# core_app.net
KiCad netlist of a schematic drawn in Altium Designer
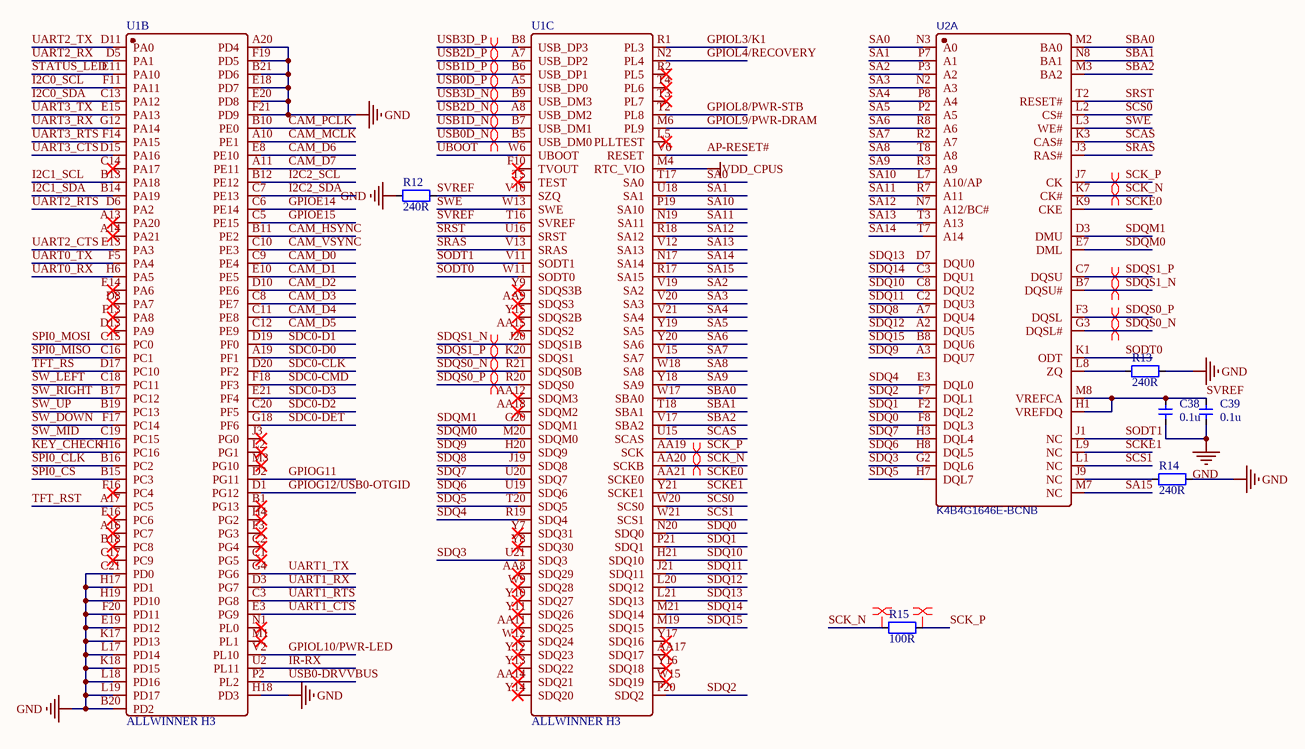
[diagram p0: core_app.SchDoc]

(export (version "E")
  (design (tool "Eeschema 10.0.6"))
  (components
    (comp (ref "C38")
      (value "0.1u")
      (footprint "C0402")
      (description "Capacitor")
      (fields (field (name "Comment") "CAP-0402"))
      (libsource (lib "core") (part "CAP-0402"))
    )
    (comp (ref "C39")
      (value "0.1u")
      (footprint "C0402")
      (description "Capacitor")
      (fields (field (name "Comment") "CAP-0402"))
      (libsource (lib "core") (part "CAP-0402"))
    )
    (comp (ref "R12")
      (value "240R")
      (footprint "R0402")
      (description "Resistor")
      (fields (field (name "Comment") "RES-0402"))
      (libsource (lib "core") (part "RES-0402"))
    )
    (comp (ref "R13")
      (value "240R")
      (footprint "R0402")
      (description "Resistor")
      (fields (field (name "Comment") "RES-0402"))
      (libsource (lib "core") (part "RES-0402"))
    )
    (comp (ref "R14")
      (value "240R")
      (footprint "R0402")
      (description "Resistor")
      (fields (field (name "Comment") "RES-0402"))
      (libsource (lib "core") (part "RES-0402"))
    )
    (comp (ref "R15")
      (value "100R")
      (footprint "R0402")
      (description "Resistor")
      (fields (field (name "Comment") "RES-0402"))
      (libsource (lib "core") (part "RES-0402"))
    )
    (comp (ref "U1")
      (value "ALLWINNER H3")
      (footprint "BGA-347_L14.0-W14.0-R21-C21-P0.65-TL")
      (libsource (lib "core") (part "allwinner H3"))
    )
    (comp (ref "U2")
      (value "K4B4G1646E-BCNB")
      (footprint "FBGA-96_L13.5-W7.5-R16-C6-P0.80-TL")
      (fields (field (name "BOM_SUPPLIER PART") "C2803248") (field (name "CONTRIBUTOR") "LCSC"))
      (libsource (lib "core") (part "K4B4G1646E-BCNB"))
    )
  )
  (nets
    (net (code "1") (name "/AP-RESET#") (class "Default")
      (node (ref "U1") (pin "V6") (pinfunction "RESET_V6") (pintype "passive"))
    )
    (net (code "2") (name "/CAM_D0") (class "Default")
      (node (ref "U1") (pin "C9") (pinfunction "PE4_C9") (pintype "passive"))
    )
    (net (code "3") (name "/CAM_D1") (class "Default")
      (node (ref "U1") (pin "E10") (pinfunction "PE5_E10") (pintype "passive"))
    )
    (net (code "4") (name "/CAM_D2") (class "Default")
      (node (ref "U1") (pin "D10") (pinfunction "PE6_D10") (pintype "passive"))
    )
    (net (code "5") (name "/CAM_D3") (class "Default")
      (node (ref "U1") (pin "C8") (pinfunction "PE7_C8") (pintype "passive"))
    )
    (net (code "6") (name "/CAM_D4") (class "Default")
      (node (ref "U1") (pin "C11") (pinfunction "PE8_C11") (pintype "passive"))
    )
    (net (code "7") (name "/CAM_D5") (class "Default")
      (node (ref "U1") (pin "C12") (pinfunction "PE9_C12") (pintype "passive"))
    )
    (net (code "8") (name "/CAM_D6") (class "Default")
      (node (ref "U1") (pin "E8") (pinfunction "PE10_E8") (pintype "passive"))
    )
    (net (code "9") (name "/CAM_D7") (class "Default")
      (node (ref "U1") (pin "A11") (pinfunction "PE11_A11") (pintype "passive"))
    )
    (net (code "10") (name "/CAM_HSYNC") (class "Default")
      (node (ref "U1") (pin "B11") (pinfunction "PE2_B11") (pintype "passive"))
    )
    (net (code "11") (name "/CAM_MCLK") (class "Default")
      (node (ref "U1") (pin "A10") (pinfunction "PE1_A10") (pintype "passive"))
    )
    (net (code "12") (name "/CAM_PCLK") (class "Default")
      (node (ref "U1") (pin "B10") (pinfunction "PE0_B10") (pintype "passive"))
    )
    (net (code "13") (name "/CAM_VSYNC") (class "Default")
      (node (ref "U1") (pin "C10") (pinfunction "PE3_C10") (pintype "passive"))
    )
    (net (code "14") (name "/GPIOE14") (class "Default")
      (node (ref "U1") (pin "C6") (pinfunction "PE14_C6") (pintype "passive"))
    )
    (net (code "15") (name "/GPIOE15") (class "Default")
      (node (ref "U1") (pin "C5") (pinfunction "PE15_C5") (pintype "passive"))
    )
    (net (code "16") (name "/GPIOG11") (class "Default")
      (node (ref "U1") (pin "D2") (pinfunction "PG11_D2") (pintype "passive"))
    )
    (net (code "17") (name "/GPIOG12{slash}USB0-OTGID") (class "Default")
      (node (ref "U1") (pin "D1") (pinfunction "PG12_D1") (pintype "passive"))
    )
    (net (code "18") (name "/GPIOL3{slash}K1") (class "Default")
      (node (ref "U1") (pin "R1") (pinfunction "PL3_R1") (pintype "passive"))
    )
    (net (code "19") (name "/GPIOL4{slash}RECOVERY") (class "Default")
      (node (ref "U1") (pin "N2") (pinfunction "PL4_N2") (pintype "passive"))
    )
    (net (code "20") (name "/GPIOL8{slash}PWR-STB") (class "Default")
      (node (ref "U1") (pin "T2") (pinfunction "PL8_T2") (pintype "passive"))
    )
    (net (code "21") (name "/GPIOL9{slash}PWR-DRAM") (class "Default")
      (node (ref "U1") (pin "M6") (pinfunction "PL9_M6") (pintype "passive"))
    )
    (net (code "22") (name "/GPIOL10{slash}PWR-LED") (class "Default")
      (node (ref "U1") (pin "V2") (pinfunction "PL10_V2") (pintype "passive"))
    )
    (net (code "23") (name "/I2C0_SCL") (class "Default")
      (node (ref "U1") (pin "F11") (pinfunction "PA11_F11") (pintype "passive"))
    )
    (net (code "24") (name "/I2C0_SDA") (class "Default")
      (node (ref "U1") (pin "C13") (pinfunction "PA12_C13") (pintype "passive"))
    )
    (net (code "25") (name "/I2C1_SCL") (class "Default")
      (node (ref "U1") (pin "B13") (pinfunction "PA18_B13") (pintype "passive"))
    )
    (net (code "26") (name "/I2C1_SDA") (class "Default")
      (node (ref "U1") (pin "B14") (pinfunction "PA19_B14") (pintype "passive"))
    )
    (net (code "27") (name "/I2C2_SCL") (class "Default")
      (node (ref "U1") (pin "B12") (pinfunction "PE12_B12") (pintype "passive"))
    )
    (net (code "28") (name "/I2C2_SDA") (class "Default")
      (node (ref "U1") (pin "C7") (pinfunction "PE13_C7") (pintype "passive"))
    )
    (net (code "29") (name "/IR-RX") (class "Default")
      (node (ref "U1") (pin "U2") (pinfunction "PL11_U2") (pintype "passive"))
    )
    (net (code "30") (name "/KEY_CHECK") (class "Default")
      (node (ref "U1") (pin "H16") (pinfunction "PC16_H16") (pintype "passive"))
    )
    (net (code "31") (name "/SA0") (class "Default")
      (node (ref "U1") (pin "T17") (pinfunction "SA0_T17") (pintype "passive"))
      (node (ref "U2") (pin "N3") (pinfunction "A0_N3") (pintype "passive"))
    )
    (net (code "32") (name "/SA1") (class "Default")
      (node (ref "U1") (pin "U18") (pinfunction "SA1_U18") (pintype "passive"))
      (node (ref "U2") (pin "P7") (pinfunction "A1_P7") (pintype "passive"))
    )
    (net (code "33") (name "/SA2") (class "Default")
      (node (ref "U1") (pin "V19") (pinfunction "SA2_V19") (pintype "passive"))
      (node (ref "U2") (pin "P3") (pinfunction "A2_P3") (pintype "passive"))
    )
    (net (code "34") (name "/SA3") (class "Default")
      (node (ref "U1") (pin "V20") (pinfunction "SA3_V20") (pintype "passive"))
      (node (ref "U2") (pin "N2") (pinfunction "A3_N2") (pintype "passive"))
    )
    (net (code "35") (name "/SA4") (class "Default")
      (node (ref "U1") (pin "V21") (pinfunction "SA4_V21") (pintype "passive"))
      (node (ref "U2") (pin "P8") (pinfunction "A4_P8") (pintype "passive"))
    )
    (net (code "36") (name "/SA5") (class "Default")
      (node (ref "U1") (pin "Y19") (pinfunction "SA5_Y19") (pintype "passive"))
      (node (ref "U2") (pin "P2") (pinfunction "A5_P2") (pintype "passive"))
    )
    (net (code "37") (name "/SA6") (class "Default")
      (node (ref "U1") (pin "Y20") (pinfunction "SA6_Y20") (pintype "passive"))
      (node (ref "U2") (pin "R8") (pinfunction "A6_R8") (pintype "passive"))
    )
    (net (code "38") (name "/SA7") (class "Default")
      (node (ref "U1") (pin "V15") (pinfunction "SA7_V15") (pintype "passive"))
      (node (ref "U2") (pin "R2") (pinfunction "A7_R2") (pintype "passive"))
    )
    (net (code "39") (name "/SA8") (class "Default")
      (node (ref "U1") (pin "W18") (pinfunction "SA8_W18") (pintype "passive"))
      (node (ref "U2") (pin "T8") (pinfunction "A8_T8") (pintype "passive"))
    )
    (net (code "40") (name "/SA9") (class "Default")
      (node (ref "U1") (pin "Y18") (pinfunction "SA9_Y18") (pintype "passive"))
      (node (ref "U2") (pin "R3") (pinfunction "A9_R3") (pintype "passive"))
    )
    (net (code "41") (name "/SA10") (class "Default")
      (node (ref "U1") (pin "P19") (pinfunction "SA10_P19") (pintype "passive"))
      (node (ref "U2") (pin "L7") (pinfunction "A10/AP_L7") (pintype "passive"))
    )
    (net (code "42") (name "/SA11") (class "Default")
      (node (ref "U1") (pin "N19") (pinfunction "SA11_N19") (pintype "passive"))
      (node (ref "U2") (pin "R7") (pinfunction "A11_R7") (pintype "passive"))
    )
    (net (code "43") (name "/SA12") (class "Default")
      (node (ref "U1") (pin "R18") (pinfunction "SA12_R18") (pintype "passive"))
      (node (ref "U2") (pin "N7") (pinfunction "A12/BC#_N7") (pintype "passive"))
    )
    (net (code "44") (name "/SA13") (class "Default")
      (node (ref "U1") (pin "V12") (pinfunction "SA13_V12") (pintype "passive"))
      (node (ref "U2") (pin "T3") (pinfunction "A13_T3") (pintype "passive"))
    )
    (net (code "45") (name "/SA14") (class "Default")
      (node (ref "U1") (pin "N17") (pinfunction "SA14_N17") (pintype "passive"))
      (node (ref "U2") (pin "T7") (pinfunction "A14_T7") (pintype "passive"))
    )
    (net (code "46") (name "/SA15") (class "Default")
      (node (ref "U1") (pin "R17") (pinfunction "SA15_R17") (pintype "passive"))
      (node (ref "U2") (pin "M7") (pinfunction "NC_M7") (pintype "passive"))
    )
    (net (code "47") (name "/SBA0") (class "Default")
      (node (ref "U1") (pin "W17") (pinfunction "SBA0_W17") (pintype "passive"))
      (node (ref "U2") (pin "M2") (pinfunction "BA0_M2") (pintype "passive"))
    )
    (net (code "48") (name "/SBA1") (class "Default")
      (node (ref "U1") (pin "T18") (pinfunction "SBA1_T18") (pintype "passive"))
      (node (ref "U2") (pin "N8") (pinfunction "BA1_N8") (pintype "passive"))
    )
    (net (code "49") (name "/SBA2") (class "Default")
      (node (ref "U1") (pin "V17") (pinfunction "SBA2_V17") (pintype "passive"))
      (node (ref "U2") (pin "M3") (pinfunction "BA2_M3") (pintype "passive"))
    )
    (net (code "50") (name "/SCAS") (class "Default")
      (node (ref "U1") (pin "U15") (pinfunction "SCAS_U15") (pintype "passive"))
      (node (ref "U2") (pin "K3") (pinfunction "CAS#_K3") (pintype "passive"))
    )
    (net (code "51") (name "/SCKE0") (class "Default")
      (node (ref "U1") (pin "AA21") (pinfunction "SCKE0_AA21") (pintype "passive"))
      (node (ref "U2") (pin "K9") (pinfunction "CKE_K9") (pintype "passive"))
    )
    (net (code "52") (name "/SCKE1") (class "Default")
      (node (ref "U1") (pin "Y21") (pinfunction "SCKE1_Y21") (pintype "passive"))
      (node (ref "U2") (pin "L9") (pinfunction "NC_L9") (pintype "passive"))
    )
    (net (code "53") (name "/SCK_N") (class "Default")
      (node (ref "R15") (pin "2") (pinfunction "2_2") (pintype "passive"))
      (node (ref "U1") (pin "AA20") (pinfunction "SCKB_AA20") (pintype "passive"))
      (node (ref "U2") (pin "K7") (pinfunction "CK#_K7") (pintype "passive"))
    )
    (net (code "54") (name "/SCK_P") (class "Default")
      (node (ref "R15") (pin "1") (pinfunction "1_1") (pintype "passive"))
      (node (ref "U1") (pin "AA19") (pinfunction "SCK_AA19") (pintype "passive"))
      (node (ref "U2") (pin "J7") (pinfunction "CK_J7") (pintype "passive"))
    )
    (net (code "55") (name "/SCS0") (class "Default")
      (node (ref "U1") (pin "W20") (pinfunction "SCS0_W20") (pintype "passive"))
      (node (ref "U2") (pin "L2") (pinfunction "CS#_L2") (pintype "passive"))
    )
    (net (code "56") (name "/SCS1") (class "Default")
      (node (ref "U1") (pin "W21") (pinfunction "SCS1_W21") (pintype "passive"))
      (node (ref "U2") (pin "L1") (pinfunction "NC_L1") (pintype "passive"))
    )
    (net (code "57") (name "/SDC0-CLK") (class "Default")
      (node (ref "U1") (pin "D20") (pinfunction "PF2_D20") (pintype "passive"))
    )
    (net (code "58") (name "/SDC0-CMD") (class "Default")
      (node (ref "U1") (pin "F18") (pinfunction "PF3_F18") (pintype "passive"))
    )
    (net (code "59") (name "/SDC0-D0") (class "Default")
      (node (ref "U1") (pin "A19") (pinfunction "PF1_A19") (pintype "passive"))
    )
    (net (code "60") (name "/SDC0-D1") (class "Default")
      (node (ref "U1") (pin "D19") (pinfunction "PF0_D19") (pintype "passive"))
    )
    (net (code "61") (name "/SDC0-D2") (class "Default")
      (node (ref "U1") (pin "C20") (pinfunction "PF5_C20") (pintype "passive"))
    )
    (net (code "62") (name "/SDC0-D3") (class "Default")
      (node (ref "U1") (pin "E21") (pinfunction "PF4_E21") (pintype "passive"))
    )
    (net (code "63") (name "/SDC0-DET") (class "Default")
      (node (ref "U1") (pin "G18") (pinfunction "PF6_G18") (pintype "passive"))
    )
    (net (code "64") (name "/SDQ0") (class "Default")
      (node (ref "U1") (pin "N20") (pinfunction "SDQ0_N20") (pintype "passive"))
      (node (ref "U2") (pin "F8") (pinfunction "DQL3_F8") (pintype "passive"))
    )
    (net (code "65") (name "/SDQ1") (class "Default")
      (node (ref "U1") (pin "P21") (pinfunction "SDQ1_P21") (pintype "passive"))
      (node (ref "U2") (pin "F2") (pinfunction "DQL2_F2") (pintype "passive"))
    )
    (net (code "66") (name "/SDQ2") (class "Default")
      (node (ref "U1") (pin "P20") (pinfunction "SDQ2_P20") (pintype "passive"))
      (node (ref "U2") (pin "F7") (pinfunction "DQL1_F7") (pintype "passive"))
    )
    (net (code "67") (name "/SDQ3") (class "Default")
      (node (ref "U1") (pin "U21") (pinfunction "SDQ3_U21") (pintype "passive"))
      (node (ref "U2") (pin "G2") (pinfunction "DQL6_G2") (pintype "passive"))
    )
    (net (code "68") (name "/SDQ4") (class "Default")
      (node (ref "U1") (pin "R19") (pinfunction "SDQ4_R19") (pintype "passive"))
      (node (ref "U2") (pin "E3") (pinfunction "DQL0_E3") (pintype "passive"))
    )
    (net (code "69") (name "/SDQ5") (class "Default")
      (node (ref "U1") (pin "T20") (pinfunction "SDQ5_T20") (pintype "passive"))
      (node (ref "U2") (pin "H7") (pinfunction "DQL7_H7") (pintype "passive"))
    )
    (net (code "70") (name "/SDQ6") (class "Default")
      (node (ref "U1") (pin "U19") (pinfunction "SDQ6_U19") (pintype "passive"))
      (node (ref "U2") (pin "H8") (pinfunction "DQL5_H8") (pintype "passive"))
    )
    (net (code "71") (name "/SDQ7") (class "Default")
      (node (ref "U1") (pin "U20") (pinfunction "SDQ7_U20") (pintype "passive"))
      (node (ref "U2") (pin "H3") (pinfunction "DQL4_H3") (pintype "passive"))
    )
    (net (code "72") (name "/SDQ8") (class "Default")
      (node (ref "U1") (pin "J19") (pinfunction "SDQ8_J19") (pintype "passive"))
      (node (ref "U2") (pin "A7") (pinfunction "DQU4_A7") (pintype "passive"))
    )
    (net (code "73") (name "/SDQ9") (class "Default")
      (node (ref "U1") (pin "H20") (pinfunction "SDQ9_H20") (pintype "passive"))
      (node (ref "U2") (pin "A3") (pinfunction "DQU7_A3") (pintype "passive"))
    )
    (net (code "74") (name "/SDQ10") (class "Default")
      (node (ref "U1") (pin "H21") (pinfunction "SDQ10_H21") (pintype "passive"))
      (node (ref "U2") (pin "C8") (pinfunction "DQU2_C8") (pintype "passive"))
    )
    (net (code "75") (name "/SDQ11") (class "Default")
      (node (ref "U1") (pin "J21") (pinfunction "SDQ11_J21") (pintype "passive"))
      (node (ref "U2") (pin "C2") (pinfunction "DQU3_C2") (pintype "passive"))
    )
    (net (code "76") (name "/SDQ12") (class "Default")
      (node (ref "U1") (pin "L20") (pinfunction "SDQ12_L20") (pintype "passive"))
      (node (ref "U2") (pin "A2") (pinfunction "DQU5_A2") (pintype "passive"))
    )
    (net (code "77") (name "/SDQ13") (class "Default")
      (node (ref "U1") (pin "L21") (pinfunction "SDQ13_L21") (pintype "passive"))
      (node (ref "U2") (pin "D7") (pinfunction "DQU0_D7") (pintype "passive"))
    )
    (net (code "78") (name "/SDQ14") (class "Default")
      (node (ref "U1") (pin "M21") (pinfunction "SDQ14_M21") (pintype "passive"))
      (node (ref "U2") (pin "C3") (pinfunction "DQU1_C3") (pintype "passive"))
    )
    (net (code "79") (name "/SDQ15") (class "Default")
      (node (ref "U1") (pin "M19") (pinfunction "SDQ15_M19") (pintype "passive"))
      (node (ref "U2") (pin "B8") (pinfunction "DQU6_B8") (pintype "passive"))
    )
    (net (code "80") (name "/SDQM0") (class "Default")
      (node (ref "U1") (pin "M20") (pinfunction "SDQM0_M20") (pintype "passive"))
      (node (ref "U2") (pin "E7") (pinfunction "DML_E7") (pintype "passive"))
    )
    (net (code "81") (name "/SDQM1") (class "Default")
      (node (ref "U1") (pin "G20") (pinfunction "SDQM1_G20") (pintype "passive"))
      (node (ref "U2") (pin "D3") (pinfunction "DMU_D3") (pintype "passive"))
    )
    (net (code "82") (name "/SDQS0_N") (class "Default")
      (node (ref "U1") (pin "R21") (pinfunction "SDQS0B_R21") (pintype "passive"))
      (node (ref "U2") (pin "G3") (pinfunction "DQSL#_G3") (pintype "passive"))
    )
    (net (code "83") (name "/SDQS0_P") (class "Default")
      (node (ref "U1") (pin "R20") (pinfunction "SDQS0_R20") (pintype "passive"))
      (node (ref "U2") (pin "F3") (pinfunction "DQSL_F3") (pintype "passive"))
    )
    (net (code "84") (name "/SDQS1_N") (class "Default")
      (node (ref "U1") (pin "J20") (pinfunction "SDQS1B_J20") (pintype "passive"))
      (node (ref "U2") (pin "B7") (pinfunction "DQSU#_B7") (pintype "passive"))
    )
    (net (code "85") (name "/SDQS1_P") (class "Default")
      (node (ref "U1") (pin "K20") (pinfunction "SDQS1_K20") (pintype "passive"))
      (node (ref "U2") (pin "C7") (pinfunction "DQSU_C7") (pintype "passive"))
    )
    (net (code "86") (name "/SODT0") (class "Default")
      (node (ref "U1") (pin "W11") (pinfunction "SODT0_W11") (pintype "passive"))
      (node (ref "U2") (pin "K1") (pinfunction "ODT_K1") (pintype "passive"))
    )
    (net (code "87") (name "/SODT1") (class "Default")
      (node (ref "U1") (pin "V11") (pinfunction "SODT1_V11") (pintype "passive"))
      (node (ref "U2") (pin "J1") (pinfunction "NC_J1") (pintype "passive"))
    )
    (net (code "88") (name "/SPI0_CLK") (class "Default")
      (node (ref "U1") (pin "B16") (pinfunction "PC2_B16") (pintype "passive"))
    )
    (net (code "89") (name "/SPI0_CS") (class "Default")
      (node (ref "U1") (pin "B15") (pinfunction "PC3_B15") (pintype "passive"))
    )
    (net (code "90") (name "/SPI0_MISO") (class "Default")
      (node (ref "U1") (pin "C16") (pinfunction "PC1_C16") (pintype "passive"))
    )
    (net (code "91") (name "/SPI0_MOSI") (class "Default")
      (node (ref "U1") (pin "C15") (pinfunction "PC0_C15") (pintype "passive"))
    )
    (net (code "92") (name "/SRAS") (class "Default")
      (node (ref "U1") (pin "V13") (pinfunction "SRAS_V13") (pintype "passive"))
      (node (ref "U2") (pin "J3") (pinfunction "RAS#_J3") (pintype "passive"))
    )
    (net (code "93") (name "/SRST") (class "Default")
      (node (ref "U1") (pin "U16") (pinfunction "SRST_U16") (pintype "passive"))
      (node (ref "U2") (pin "T2") (pinfunction "RESET#_T2") (pintype "passive"))
    )
    (net (code "94") (name "/STATUS_LED") (class "Default")
      (node (ref "U1") (pin "E11") (pinfunction "PA10_E11") (pintype "passive"))
    )
    (net (code "95") (name "/SVREF") (class "Default")
      (node (ref "C38") (pin "2") (pinfunction "2_2") (pintype "passive"))
      (node (ref "C39") (pin "2") (pinfunction "2_2") (pintype "passive"))
      (node (ref "R12") (pin "1") (pinfunction "1_1") (pintype "passive"))
      (node (ref "U1") (pin "T16") (pinfunction "SVREF_T16") (pintype "passive"))
      (node (ref "U1") (pin "V10") (pinfunction "SZQ_V10") (pintype "passive"))
      (node (ref "U2") (pin "H1") (pinfunction "VREFDQ_H1") (pintype "passive"))
      (node (ref "U2") (pin "M8") (pinfunction "VREFCA_M8") (pintype "passive"))
    )
    (net (code "96") (name "/SWE") (class "Default")
      (node (ref "U1") (pin "W13") (pinfunction "SWE_W13") (pintype "passive"))
      (node (ref "U2") (pin "L3") (pinfunction "WE#_L3") (pintype "passive"))
    )
    (net (code "97") (name "/SW_DOWN") (class "Default")
      (node (ref "U1") (pin "F17") (pinfunction "PC14_F17") (pintype "passive"))
    )
    (net (code "98") (name "/SW_LEFT") (class "Default")
      (node (ref "U1") (pin "C18") (pinfunction "PC11_C18") (pintype "passive"))
    )
    (net (code "99") (name "/SW_MID") (class "Default")
      (node (ref "U1") (pin "C19") (pinfunction "PC15_C19") (pintype "passive"))
    )
    (net (code "100") (name "/SW_RIGHT") (class "Default")
      (node (ref "U1") (pin "B17") (pinfunction "PC12_B17") (pintype "passive"))
    )
    (net (code "101") (name "/SW_UP") (class "Default")
      (node (ref "U1") (pin "B19") (pinfunction "PC13_B19") (pintype "passive"))
    )
    (net (code "102") (name "/TFT_RS") (class "Default")
      (node (ref "U1") (pin "D17") (pinfunction "PC10_D17") (pintype "passive"))
    )
    (net (code "103") (name "/TFT_RST") (class "Default")
      (node (ref "U1") (pin "A17") (pinfunction "PC5_A17") (pintype "passive"))
    )
    (net (code "104") (name "/UART0_RX") (class "Default")
      (node (ref "U1") (pin "H6") (pinfunction "PA5_H6") (pintype "passive"))
    )
    (net (code "105") (name "/UART0_TX") (class "Default")
      (node (ref "U1") (pin "F5") (pinfunction "PA4_F5") (pintype "passive"))
    )
    (net (code "106") (name "/UART1_CTS") (class "Default")
      (node (ref "U1") (pin "E3") (pinfunction "PG9_E3") (pintype "passive"))
    )
    (net (code "107") (name "/UART1_RTS") (class "Default")
      (node (ref "U1") (pin "C3") (pinfunction "PG8_C3") (pintype "passive"))
    )
    (net (code "108") (name "/UART1_RX") (class "Default")
      (node (ref "U1") (pin "D3") (pinfunction "PG7_D3") (pintype "passive"))
    )
    (net (code "109") (name "/UART1_TX") (class "Default")
      (node (ref "U1") (pin "G4") (pinfunction "PG6_G4") (pintype "passive"))
    )
    (net (code "110") (name "/UART2_CTS") (class "Default")
      (node (ref "U1") (pin "E13") (pinfunction "PA3_E13") (pintype "passive"))
    )
    (net (code "111") (name "/UART2_RTS") (class "Default")
      (node (ref "U1") (pin "D6") (pinfunction "PA2_D6") (pintype "passive"))
    )
    (net (code "112") (name "/UART2_RX") (class "Default")
      (node (ref "U1") (pin "D5") (pinfunction "PA1_D5") (pintype "passive"))
    )
    (net (code "113") (name "/UART2_TX") (class "Default")
      (node (ref "U1") (pin "D11") (pinfunction "PA0_D11") (pintype "passive"))
    )
    (net (code "114") (name "/UART3_CTS") (class "Default")
      (node (ref "U1") (pin "D15") (pinfunction "PA16_D15") (pintype "passive"))
    )
    (net (code "115") (name "/UART3_RTS") (class "Default")
      (node (ref "U1") (pin "F14") (pinfunction "PA15_F14") (pintype "passive"))
    )
    (net (code "116") (name "/UART3_RX") (class "Default")
      (node (ref "U1") (pin "G12") (pinfunction "PA14_G12") (pintype "passive"))
    )
    (net (code "117") (name "/UART3_TX") (class "Default")
      (node (ref "U1") (pin "E15") (pinfunction "PA13_E15") (pintype "passive"))
    )
    (net (code "118") (name "/UBOOT") (class "Default")
      (node (ref "U1") (pin "W6") (pinfunction "UBOOT_W6") (pintype "passive"))
    )
    (net (code "119") (name "/USB0-DRVVBUS") (class "Default")
      (node (ref "U1") (pin "P2") (pinfunction "PL2_P2") (pintype "passive"))
    )
    (net (code "120") (name "/USB0D_N") (class "Default")
      (node (ref "U1") (pin "B5") (pinfunction "USB_DM0_B5") (pintype "passive"))
    )
    (net (code "121") (name "/USB0D_P") (class "Default")
      (node (ref "U1") (pin "A5") (pinfunction "USB_DP0_A5") (pintype "passive"))
    )
    (net (code "122") (name "/USB1D_N") (class "Default")
      (node (ref "U1") (pin "B7") (pinfunction "USB_DM1_B7") (pintype "passive"))
    )
    (net (code "123") (name "/USB1D_P") (class "Default")
      (node (ref "U1") (pin "B6") (pinfunction "USB_DP1_B6") (pintype "passive"))
    )
    (net (code "124") (name "/USB2D_N") (class "Default")
      (node (ref "U1") (pin "A8") (pinfunction "USB_DM2_A8") (pintype "passive"))
    )
    (net (code "125") (name "/USB2D_P") (class "Default")
      (node (ref "U1") (pin "A7") (pinfunction "USB_DP2_A7") (pintype "passive"))
    )
    (net (code "126") (name "/USB3D_N") (class "Default")
      (node (ref "U1") (pin "B9") (pinfunction "USB_DM3_B9") (pintype "passive"))
    )
    (net (code "127") (name "/USB3D_P") (class "Default")
      (node (ref "U1") (pin "B8") (pinfunction "USB_DP3_B8") (pintype "passive"))
    )
    (net (code "128") (name "GND") (class "Default")
      (node (ref "C38") (pin "1") (pinfunction "1_1") (pintype "passive"))
      (node (ref "C39") (pin "1") (pinfunction "1_1") (pintype "passive"))
      (node (ref "R12") (pin "2") (pinfunction "2_2") (pintype "passive"))
      (node (ref "R13") (pin "1") (pinfunction "1_1") (pintype "passive"))
      (node (ref "R14") (pin "1") (pinfunction "1_1") (pintype "passive"))
      (node (ref "U1") (pin "A20") (pinfunction "PD4_A20") (pintype "passive"))
      (node (ref "U1") (pin "B20") (pinfunction "PD2_B20") (pintype "passive"))
      (node (ref "U1") (pin "B21") (pinfunction "PD6_B21") (pintype "passive"))
      (node (ref "U1") (pin "C21") (pinfunction "PD0_C21") (pintype "passive"))
      (node (ref "U1") (pin "E18") (pinfunction "PD7_E18") (pintype "passive"))
      (node (ref "U1") (pin "E19") (pinfunction "PD12_E19") (pintype "passive"))
      (node (ref "U1") (pin "E20") (pinfunction "PD8_E20") (pintype "passive"))
      (node (ref "U1") (pin "F19") (pinfunction "PD5_F19") (pintype "passive"))
      (node (ref "U1") (pin "F20") (pinfunction "PD11_F20") (pintype "passive"))
      (node (ref "U1") (pin "F21") (pinfunction "PD9_F21") (pintype "passive"))
      (node (ref "U1") (pin "H17") (pinfunction "PD1_H17") (pintype "passive"))
      (node (ref "U1") (pin "H18") (pinfunction "PD3_H18") (pintype "passive"))
      (node (ref "U1") (pin "H19") (pinfunction "PD10_H19") (pintype "passive"))
      (node (ref "U1") (pin "K17") (pinfunction "PD13_K17") (pintype "passive"))
      (node (ref "U1") (pin "K18") (pinfunction "PD15_K18") (pintype "passive"))
      (node (ref "U1") (pin "L17") (pinfunction "PD14_L17") (pintype "passive"))
      (node (ref "U1") (pin "L18") (pinfunction "PD16_L18") (pintype "passive"))
      (node (ref "U1") (pin "L19") (pinfunction "PD17_L19") (pintype "passive"))
    )
    (net (code "129") (name "Net-(R14-Pad2)") (class "Default")
      (node (ref "R14") (pin "2") (pinfunction "2_2") (pintype "passive"))
      (node (ref "U2") (pin "J9") (pinfunction "NC_J9") (pintype "passive"))
    )
    (net (code "130") (name "Net-(U2A-ZQ)") (class "Default")
      (node (ref "R13") (pin "2") (pinfunction "2_2") (pintype "passive"))
      (node (ref "U2") (pin "L8") (pinfunction "ZQ_L8") (pintype "passive"))
    )
    (net (code "131") (name "VDD_CPUS") (class "Default")
      (node (ref "U1") (pin "M4") (pinfunction "RTC_VIO_M4") (pintype "passive"))
    )
    (net (code "132") (name "unconnected-(U1B-PA6-PadE14)") (class "Default")
      (node (ref "U1") (pin "E14") (pinfunction "PA6_E14") (pintype "passive+no_connect"))
    )
    (net (code "133") (name "unconnected-(U1B-PA7-PadD8)") (class "Default")
      (node (ref "U1") (pin "D8") (pinfunction "PA7_D8") (pintype "passive+no_connect"))
    )
    (net (code "134") (name "unconnected-(U1B-PA8-PadF13)") (class "Default")
      (node (ref "U1") (pin "F13") (pinfunction "PA8_F13") (pintype "passive+no_connect"))
    )
    (net (code "135") (name "unconnected-(U1B-PA9-PadD13)") (class "Default")
      (node (ref "U1") (pin "D13") (pinfunction "PA9_D13") (pintype "passive+no_connect"))
    )
    (net (code "136") (name "unconnected-(U1B-PA17-PadC14)") (class "Default")
      (node (ref "U1") (pin "C14") (pinfunction "PA17_C14") (pintype "passive+no_connect"))
    )
    (net (code "137") (name "unconnected-(U1B-PA20-PadA13)") (class "Default")
      (node (ref "U1") (pin "A13") (pinfunction "PA20_A13") (pintype "passive+no_connect"))
    )
    (net (code "138") (name "unconnected-(U1B-PA21-PadA14)") (class "Default")
      (node (ref "U1") (pin "A14") (pinfunction "PA21_A14") (pintype "passive+no_connect"))
    )
    (net (code "139") (name "unconnected-(U1B-PC4-PadF16)") (class "Default")
      (node (ref "U1") (pin "F16") (pinfunction "PC4_F16") (pintype "passive+no_connect"))
    )
    (net (code "140") (name "unconnected-(U1B-PC6-PadE16)") (class "Default")
      (node (ref "U1") (pin "E16") (pinfunction "PC6_E16") (pintype "passive+no_connect"))
    )
    (net (code "141") (name "unconnected-(U1B-PC7-PadA16)") (class "Default")
      (node (ref "U1") (pin "A16") (pinfunction "PC7_A16") (pintype "passive+no_connect"))
    )
    (net (code "142") (name "unconnected-(U1B-PC8-PadB18)") (class "Default")
      (node (ref "U1") (pin "B18") (pinfunction "PC8_B18") (pintype "passive+no_connect"))
    )
    (net (code "143") (name "unconnected-(U1B-PC9-PadC17)") (class "Default")
      (node (ref "U1") (pin "C17") (pinfunction "PC9_C17") (pintype "passive+no_connect"))
    )
    (net (code "144") (name "unconnected-(U1B-PG0-PadJ3)") (class "Default")
      (node (ref "U1") (pin "J3") (pinfunction "PG0_J3") (pintype "passive+no_connect"))
    )
    (net (code "145") (name "unconnected-(U1B-PG1-PadL2)") (class "Default")
      (node (ref "U1") (pin "L2") (pinfunction "PG1_L2") (pintype "passive+no_connect"))
    )
    (net (code "146") (name "unconnected-(U1B-PG2-PadH4)") (class "Default")
      (node (ref "U1") (pin "H4") (pinfunction "PG2_H4") (pintype "passive+no_connect"))
    )
    (net (code "147") (name "unconnected-(U1B-PG3-PadF3)") (class "Default")
      (node (ref "U1") (pin "F3") (pinfunction "PG3_F3") (pintype "passive+no_connect"))
    )
    (net (code "148") (name "unconnected-(U1B-PG4-PadC2)") (class "Default")
      (node (ref "U1") (pin "C2") (pinfunction "PG4_C2") (pintype "passive+no_connect"))
    )
    (net (code "149") (name "unconnected-(U1B-PG5-PadC1)") (class "Default")
      (node (ref "U1") (pin "C1") (pinfunction "PG5_C1") (pintype "passive+no_connect"))
    )
    (net (code "150") (name "unconnected-(U1B-PG10-PadM3)") (class "Default")
      (node (ref "U1") (pin "M3") (pinfunction "PG10_M3") (pintype "passive+no_connect"))
    )
    (net (code "151") (name "unconnected-(U1B-PG13-PadB1)") (class "Default")
      (node (ref "U1") (pin "B1") (pinfunction "PG13_B1") (pintype "passive+no_connect"))
    )
    (net (code "152") (name "unconnected-(U1B-PL0-PadN1)") (class "Default")
      (node (ref "U1") (pin "N1") (pinfunction "PL0_N1") (pintype "passive+no_connect"))
    )
    (net (code "153") (name "unconnected-(U1B-PL1-PadM1)") (class "Default")
      (node (ref "U1") (pin "M1") (pinfunction "PL1_M1") (pintype "passive+no_connect"))
    )
    (net (code "154") (name "unconnected-(U1C-PL5-PadR2)") (class "Default")
      (node (ref "U1") (pin "R2") (pinfunction "PL5_R2") (pintype "passive+no_connect"))
    )
    (net (code "155") (name "unconnected-(U1C-PL6-PadT4)") (class "Default")
      (node (ref "U1") (pin "T4") (pinfunction "PL6_T4") (pintype "passive+no_connect"))
    )
    (net (code "156") (name "unconnected-(U1C-PL7-PadT3)") (class "Default")
      (node (ref "U1") (pin "T3") (pinfunction "PL7_T3") (pintype "passive+no_connect"))
    )
    (net (code "157") (name "unconnected-(U1C-PLLTEST-PadL5)") (class "Default")
      (node (ref "U1") (pin "L5") (pinfunction "PLLTEST_L5") (pintype "passive+no_connect"))
    )
    (net (code "158") (name "unconnected-(U1C-SDQ16-PadY17)") (class "Default")
      (node (ref "U1") (pin "Y17") (pinfunction "SDQ16_Y17") (pintype "passive+no_connect"))
    )
    (net (code "159") (name "unconnected-(U1C-SDQ17-PadAA17)") (class "Default")
      (node (ref "U1") (pin "AA17") (pinfunction "SDQ17_AA17") (pintype "passive+no_connect"))
    )
    (net (code "160") (name "unconnected-(U1C-SDQ18-PadY16)") (class "Default")
      (node (ref "U1") (pin "Y16") (pinfunction "SDQ18_Y16") (pintype "passive+no_connect"))
    )
    (net (code "161") (name "unconnected-(U1C-SDQ19-PadW15)") (class "Default")
      (node (ref "U1") (pin "W15") (pinfunction "SDQ19_W15") (pintype "passive+no_connect"))
    )
    (net (code "162") (name "unconnected-(U1C-SDQ20-PadY14)") (class "Default")
      (node (ref "U1") (pin "Y14") (pinfunction "SDQ20_Y14") (pintype "passive+no_connect"))
    )
    (net (code "163") (name "unconnected-(U1C-SDQ21-PadAA14)") (class "Default")
      (node (ref "U1") (pin "AA14") (pinfunction "SDQ21_AA14") (pintype "passive+no_connect"))
    )
    (net (code "164") (name "unconnected-(U1C-SDQ22-PadY13)") (class "Default")
      (node (ref "U1") (pin "Y13") (pinfunction "SDQ22_Y13") (pintype "passive+no_connect"))
    )
    (net (code "165") (name "unconnected-(U1C-SDQ23-PadY12)") (class "Default")
      (node (ref "U1") (pin "Y12") (pinfunction "SDQ23_Y12") (pintype "passive+no_connect"))
    )
    (net (code "166") (name "unconnected-(U1C-SDQ24-PadW12)") (class "Default")
      (node (ref "U1") (pin "W12") (pinfunction "SDQ24_W12") (pintype "passive+no_connect"))
    )
    (net (code "167") (name "unconnected-(U1C-SDQ25-PadAA11)") (class "Default")
      (node (ref "U1") (pin "AA11") (pinfunction "SDQ25_AA11") (pintype "passive+no_connect"))
    )
    (net (code "168") (name "unconnected-(U1C-SDQ26-PadY11)") (class "Default")
      (node (ref "U1") (pin "Y11") (pinfunction "SDQ26_Y11") (pintype "passive+no_connect"))
    )
    (net (code "169") (name "unconnected-(U1C-SDQ27-PadY10)") (class "Default")
      (node (ref "U1") (pin "Y10") (pinfunction "SDQ27_Y10") (pintype "passive+no_connect"))
    )
    (net (code "170") (name "unconnected-(U1C-SDQ28-PadW9)") (class "Default")
      (node (ref "U1") (pin "W9") (pinfunction "SDQ28_W9") (pintype "passive+no_connect"))
    )
    (net (code "171") (name "unconnected-(U1C-SDQ29-PadAA8)") (class "Default")
      (node (ref "U1") (pin "AA8") (pinfunction "SDQ29_AA8") (pintype "passive+no_connect"))
    )
    (net (code "172") (name "unconnected-(U1C-SDQ30-PadY8)") (class "Default")
      (node (ref "U1") (pin "Y8") (pinfunction "SDQ30_Y8") (pintype "passive+no_connect"))
    )
    (net (code "173") (name "unconnected-(U1C-SDQ31-PadY7)") (class "Default")
      (node (ref "U1") (pin "Y7") (pinfunction "SDQ31_Y7") (pintype "passive+no_connect"))
    )
    (net (code "174") (name "unconnected-(U1C-SDQM2-PadAA18)") (class "Default")
      (node (ref "U1") (pin "AA18") (pinfunction "SDQM2_AA18") (pintype "passive+no_connect"))
    )
    (net (code "175") (name "unconnected-(U1C-SDQM3-PadAA12)") (class "Default")
      (node (ref "U1") (pin "AA12") (pinfunction "SDQM3_AA12") (pintype "passive+no_connect"))
    )
    (net (code "176") (name "unconnected-(U1C-SDQS2-PadAA15)") (class "Default")
      (node (ref "U1") (pin "AA15") (pinfunction "SDQS2_AA15") (pintype "passive+no_connect"))
    )
    (net (code "177") (name "unconnected-(U1C-SDQS2B-PadY15)") (class "Default")
      (node (ref "U1") (pin "Y15") (pinfunction "SDQS2B_Y15") (pintype "passive+no_connect"))
    )
    (net (code "178") (name "unconnected-(U1C-SDQS3-PadAA9)") (class "Default")
      (node (ref "U1") (pin "AA9") (pinfunction "SDQS3_AA9") (pintype "passive+no_connect"))
    )
    (net (code "179") (name "unconnected-(U1C-SDQS3B-PadY9)") (class "Default")
      (node (ref "U1") (pin "Y9") (pinfunction "SDQS3B_Y9") (pintype "passive+no_connect"))
    )
    (net (code "180") (name "unconnected-(U1C-TEST-PadT5)") (class "Default")
      (node (ref "U1") (pin "T5") (pinfunction "TEST_T5") (pintype "passive+no_connect"))
    )
    (net (code "181") (name "unconnected-(U1C-TVOUT-PadF10)") (class "Default")
      (node (ref "U1") (pin "F10") (pinfunction "TVOUT_F10") (pintype "passive+no_connect"))
    )
  )
)
